# Controller_Schematic.net
KiCad netlist of a schematic drawn in Altium Designer
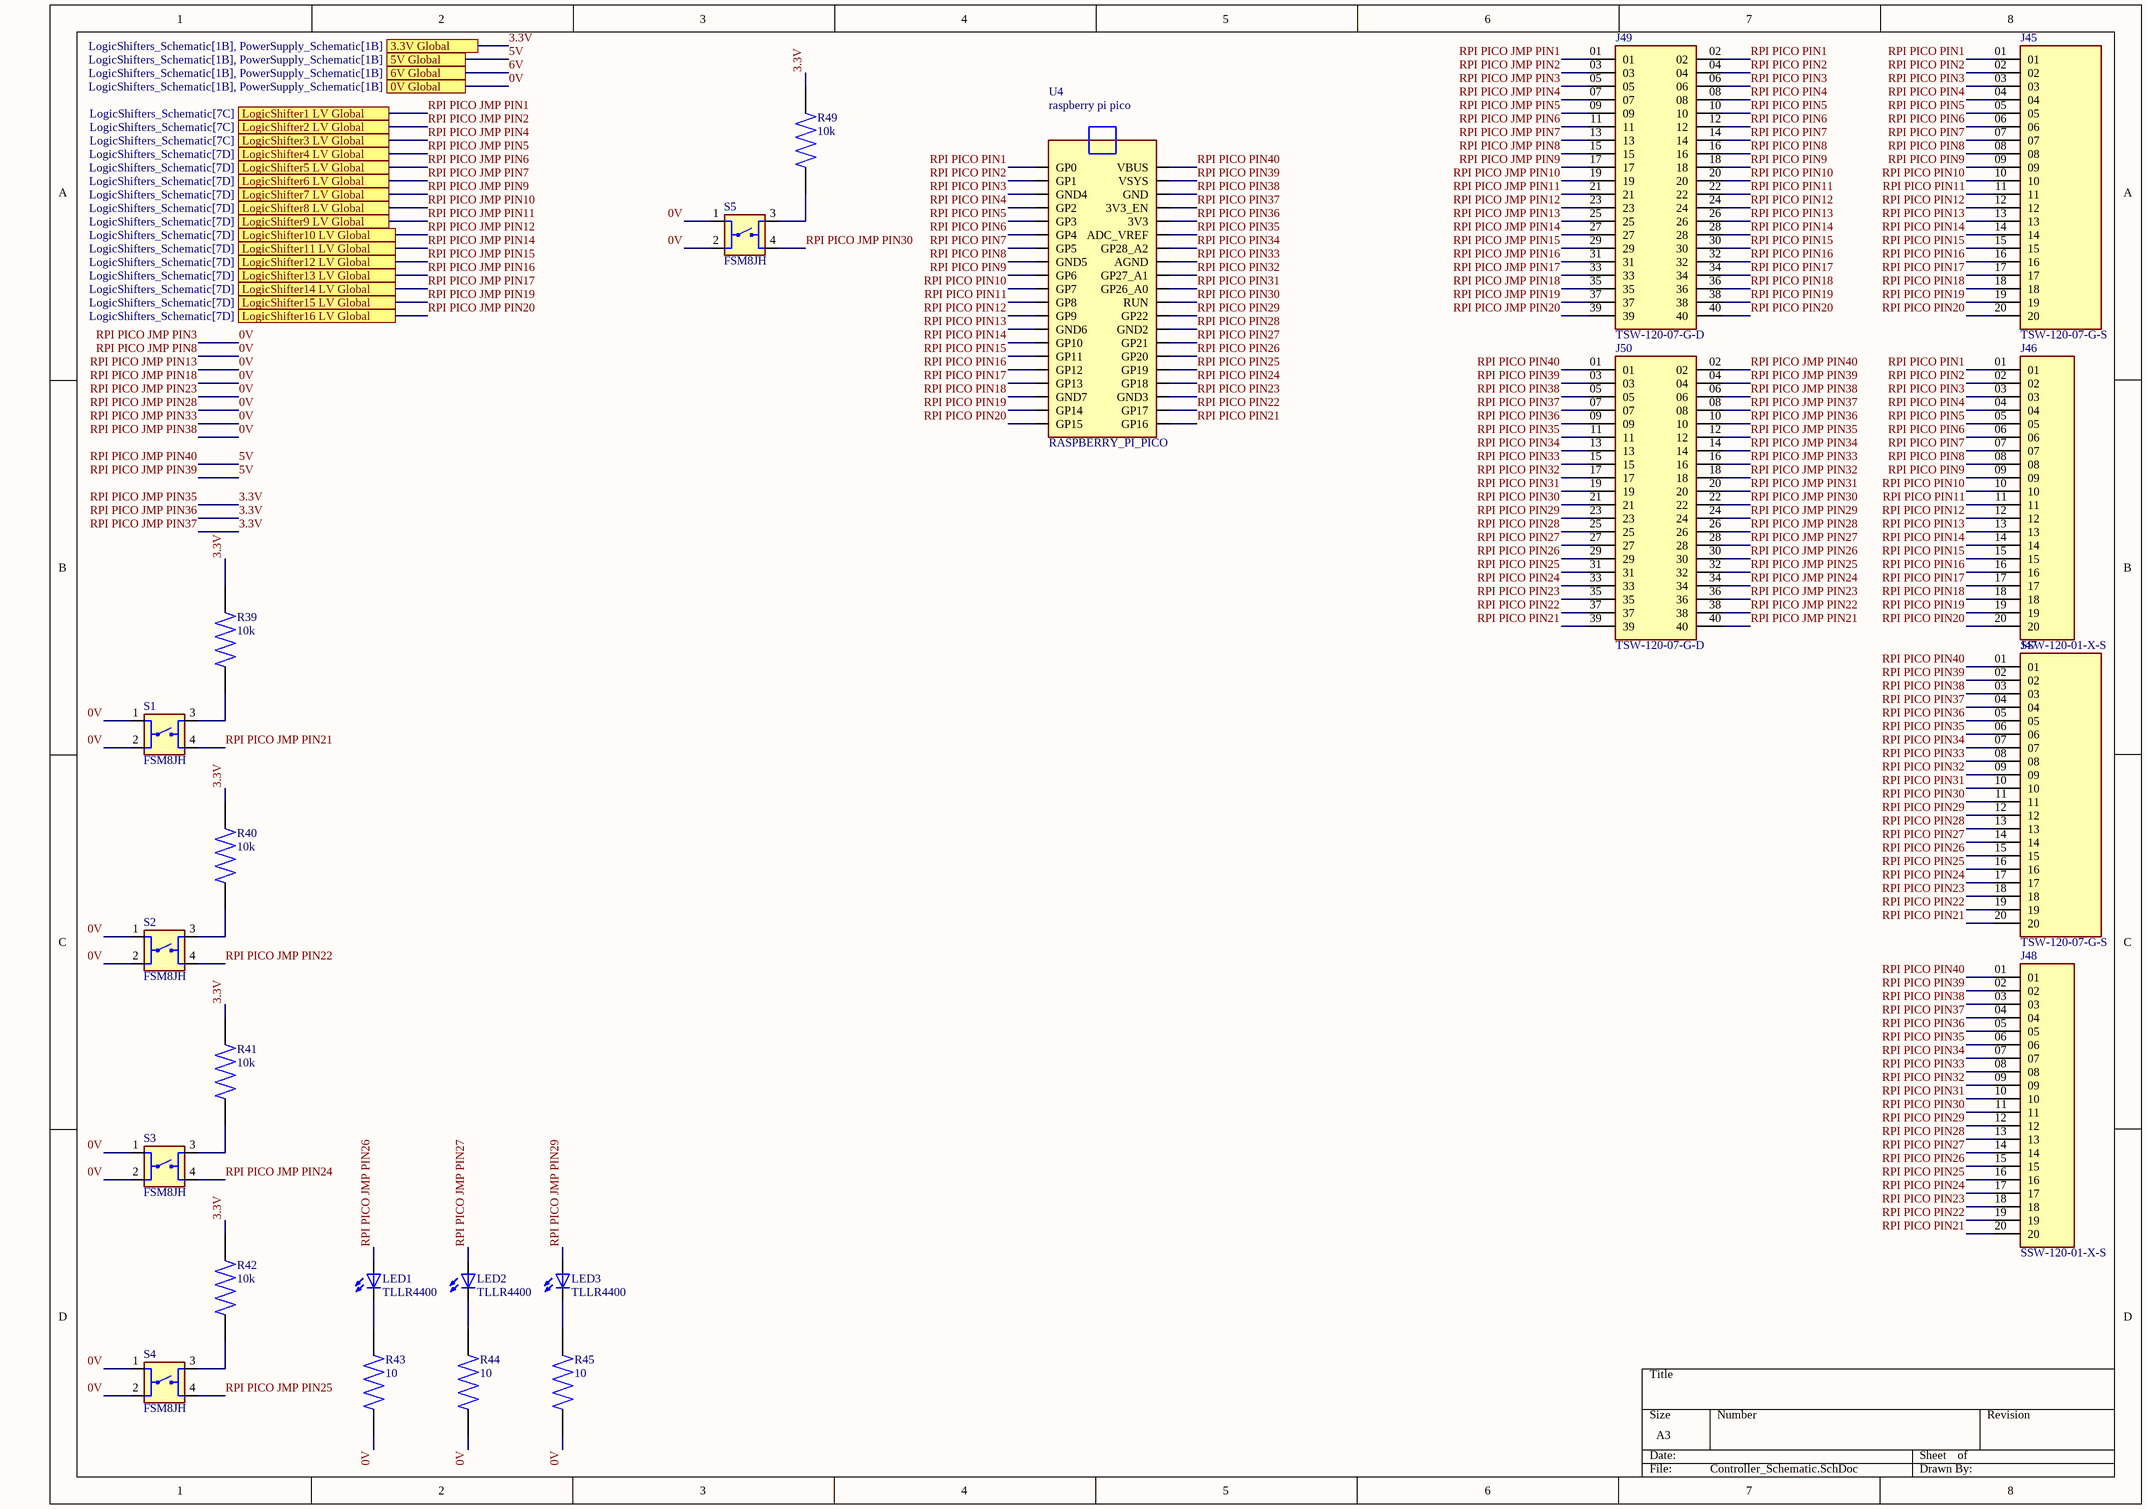
[diagram p0: Controller_Schematic.SchDoc]

(export (version "E")
  (design (tool "Eeschema 10.0.6"))
  (components
    (comp (ref "J45")
      (value "TSW-120-07-G-S")
      (footprint "SAMTEC_TSW-120-07-G-S")
      (fields (field (name "MF") "Samtec"))
      (libsource (lib "TSW-120-07-G-S") (part "TSW-120-07-G-S"))
    )
    (comp (ref "J46")
      (value "SSW-120-01-X-S")
      (footprint "SAMTEC_SSW-120-01-X-S")
      (description "SSW - Samtec 2.54mm Single Row Straight Socket Strip 8.5 Profile - Fast Stock")
      (fields (field (name "MF") "Samtec") (field (name "MP") "SSW-120-01-G-S"))
      (libsource (lib "SSW-120-01-G-S") (part "SSW-120-01-X-S"))
    )
    (comp (ref "J47")
      (value "TSW-120-07-G-S")
      (footprint "SAMTEC_TSW-120-07-G-S")
      (fields (field (name "MF") "Samtec"))
      (libsource (lib "TSW-120-07-G-S") (part "TSW-120-07-G-S"))
    )
    (comp (ref "J48")
      (value "SSW-120-01-X-S")
      (footprint "SAMTEC_SSW-120-01-X-S")
      (description "SSW - Samtec 2.54mm Single Row Straight Socket Strip 8.5 Profile - Fast Stock")
      (fields (field (name "MF") "Samtec") (field (name "MP") "SSW-120-01-G-S"))
      (libsource (lib "SSW-120-01-G-S") (part "SSW-120-01-X-S"))
    )
    (comp (ref "J49")
      (value "TSW-120-07-G-D")
      (footprint "SAMTEC_TSW-120-07-G-D")
      (fields (field (name "MF") "Samtec"))
      (libsource (lib "TSW-120-07-G-D") (part "TSW-120-07-G-D"))
    )
    (comp (ref "J50")
      (value "TSW-120-07-G-D")
      (footprint "SAMTEC_TSW-120-07-G-D")
      (fields (field (name "MF") "Samtec"))
      (libsource (lib "TSW-120-07-G-D") (part "TSW-120-07-G-D"))
    )
    (comp (ref "LED1")
      (value "TLLR4400")
      (footprint "LED3MM")
      (description "Red 619nm LED Indication - Discrete 1.9V Radial")
      (fields (field (name "MF") "Vishay"))
      (libsource (lib "LED-TLLR4400") (part "TLLR4400"))
    )
    (comp (ref "LED2")
      (value "TLLR4400")
      (footprint "LED3MM")
      (description "Red 619nm LED Indication - Discrete 1.9V Radial")
      (fields (field (name "MF") "Vishay"))
      (libsource (lib "LED-TLLR4400") (part "TLLR4400"))
    )
    (comp (ref "LED3")
      (value "TLLR4400")
      (footprint "LED3MM")
      (description "Red 619nm LED Indication - Discrete 1.9V Radial")
      (fields (field (name "MF") "Vishay"))
      (libsource (lib "LED-TLLR4400") (part "TLLR4400"))
    )
    (comp (ref "R39")
      (value "10k")
      (footprint "RESAD700W45L350D185")
      (description "1 MOhms Â±5% 0.25W, 1/4W Through Hole Resistor Axial - Carbon Film")
      (fields (field (name "MF") "TE Connectivity") (field (name "MP") "3-1623927-1"))
      (libsource (lib "RES-DIP-0.25W") (part "3-1623927-1"))
    )
    (comp (ref "R40")
      (value "10k")
      (footprint "RESAD700W45L350D185")
      (description "1 MOhms Â±5% 0.25W, 1/4W Through Hole Resistor Axial - Carbon Film")
      (fields (field (name "MF") "TE Connectivity") (field (name "MP") "3-1623927-1"))
      (libsource (lib "RES-DIP-0.25W") (part "3-1623927-1"))
    )
    (comp (ref "R41")
      (value "10k")
      (footprint "RESAD700W45L350D185")
      (description "1 MOhms Â±5% 0.25W, 1/4W Through Hole Resistor Axial - Carbon Film")
      (fields (field (name "MF") "TE Connectivity") (field (name "MP") "3-1623927-1"))
      (libsource (lib "RES-DIP-0.25W") (part "3-1623927-1"))
    )
    (comp (ref "R42")
      (value "10k")
      (footprint "RESAD700W45L350D185")
      (description "1 MOhms Â±5% 0.25W, 1/4W Through Hole Resistor Axial - Carbon Film")
      (fields (field (name "MF") "TE Connectivity") (field (name "MP") "3-1623927-1"))
      (libsource (lib "RES-DIP-0.25W") (part "3-1623927-1"))
    )
    (comp (ref "R43")
      (value "10")
      (footprint "RESAD700W45L350D185")
      (description "1 MOhms Â±5% 0.25W, 1/4W Through Hole Resistor Axial - Carbon Film")
      (fields (field (name "MF") "TE Connectivity") (field (name "MP") "3-1623927-1"))
      (libsource (lib "RES-DIP-0.25W") (part "3-1623927-1"))
    )
    (comp (ref "R44")
      (value "10")
      (footprint "RESAD700W45L350D185")
      (description "1 MOhms Â±5% 0.25W, 1/4W Through Hole Resistor Axial - Carbon Film")
      (fields (field (name "MF") "TE Connectivity") (field (name "MP") "3-1623927-1"))
      (libsource (lib "RES-DIP-0.25W") (part "3-1623927-1"))
    )
    (comp (ref "R45")
      (value "10")
      (footprint "RESAD700W45L350D185")
      (description "1 MOhms Â±5% 0.25W, 1/4W Through Hole Resistor Axial - Carbon Film")
      (fields (field (name "MF") "TE Connectivity") (field (name "MP") "3-1623927-1"))
      (libsource (lib "RES-DIP-0.25W") (part "3-1623927-1"))
    )
    (comp (ref "R49")
      (value "10k")
      (footprint "RESAD700W45L350D185")
      (description "1 MOhms Â±5% 0.25W, 1/4W Through Hole Resistor Axial - Carbon Film")
      (fields (field (name "MF") "TE Connectivity") (field (name "MP") "3-1623927-1"))
      (libsource (lib "RES-DIP-0.25W") (part "3-1623927-1"))
    )
    (comp (ref "S1")
      (value "FSM8JH")
      (footprint "SW_FSM8JH")
      (description "Tactile Switch SPST-NO Top Actuated Through Hole")
      (fields (field (name "MF") "TE Connectivity"))
      (libsource (lib "PushButton-FSM8JH") (part "FSM8JH"))
    )
    (comp (ref "S2")
      (value "FSM8JH")
      (footprint "SW_FSM8JH")
      (description "Tactile Switch SPST-NO Top Actuated Through Hole")
      (fields (field (name "MF") "TE Connectivity"))
      (libsource (lib "PushButton-FSM8JH") (part "FSM8JH"))
    )
    (comp (ref "S3")
      (value "FSM8JH")
      (footprint "SW_FSM8JH")
      (description "Tactile Switch SPST-NO Top Actuated Through Hole")
      (fields (field (name "MF") "TE Connectivity"))
      (libsource (lib "PushButton-FSM8JH") (part "FSM8JH"))
    )
    (comp (ref "S4")
      (value "FSM8JH")
      (footprint "SW_FSM8JH")
      (description "Tactile Switch SPST-NO Top Actuated Through Hole")
      (fields (field (name "MF") "TE Connectivity"))
      (libsource (lib "PushButton-FSM8JH") (part "FSM8JH"))
    )
    (comp (ref "S5")
      (value "FSM8JH")
      (footprint "SW_FSM8JH")
      (description "Tactile Switch SPST-NO Top Actuated Through Hole")
      (fields (field (name "MF") "TE Connectivity"))
      (libsource (lib "PushButton-FSM8JH") (part "FSM8JH"))
    )
    (comp (ref "U4")
      (value "RASPBERRY_PI_PICO")
      (footprint "RASPBERRY_PI_PICO")
      (fields (field (name "MF") "Raspberry Pi") (field (name "MP") "RASPBERRY PI PICO"))
      (libsource (lib "RASPBERRY_PI_PICO") (part "RASPBERRY_PI_PICO"))
    )
  )
  (nets
    (net (code "1") (name "/0V") (class "Default")
      (node (ref "J49") (pin "05") (pinfunction "05_05") (pintype "passive"))
      (node (ref "J49") (pin "15") (pinfunction "15_15") (pintype "passive"))
      (node (ref "J49") (pin "25") (pinfunction "25_25") (pintype "passive"))
      (node (ref "J49") (pin "35") (pinfunction "35_35") (pintype "passive"))
      (node (ref "J50") (pin "06") (pinfunction "06_06") (pintype "passive"))
      (node (ref "J50") (pin "16") (pinfunction "16_16") (pintype "passive"))
      (node (ref "J50") (pin "26") (pinfunction "26_26") (pintype "passive"))
      (node (ref "J50") (pin "36") (pinfunction "36_36") (pintype "passive"))
      (node (ref "R43") (pin "1") (pinfunction "1_1") (pintype "passive"))
      (node (ref "R44") (pin "1") (pinfunction "1_1") (pintype "passive"))
      (node (ref "R45") (pin "1") (pinfunction "1_1") (pintype "passive"))
      (node (ref "S1") (pin "1") (pinfunction "1_1") (pintype "passive"))
      (node (ref "S1") (pin "2") (pinfunction "2_2") (pintype "passive"))
      (node (ref "S2") (pin "1") (pinfunction "1_1") (pintype "passive"))
      (node (ref "S2") (pin "2") (pinfunction "2_2") (pintype "passive"))
      (node (ref "S3") (pin "1") (pinfunction "1_1") (pintype "passive"))
      (node (ref "S3") (pin "2") (pinfunction "2_2") (pintype "passive"))
      (node (ref "S4") (pin "1") (pinfunction "1_1") (pintype "passive"))
      (node (ref "S4") (pin "2") (pinfunction "2_2") (pintype "passive"))
      (node (ref "S5") (pin "1") (pinfunction "1_1") (pintype "passive"))
      (node (ref "S5") (pin "2") (pinfunction "2_2") (pintype "passive"))
    )
    (net (code "2") (name "/3.3V") (class "Default")
      (node (ref "J50") (pin "08") (pinfunction "08_08") (pintype "passive"))
      (node (ref "J50") (pin "10") (pinfunction "10_10") (pintype "passive"))
      (node (ref "J50") (pin "12") (pinfunction "12_12") (pintype "passive"))
      (node (ref "R39") (pin "2") (pinfunction "2_2") (pintype "passive"))
      (node (ref "R40") (pin "2") (pinfunction "2_2") (pintype "passive"))
      (node (ref "R41") (pin "2") (pinfunction "2_2") (pintype "passive"))
      (node (ref "R42") (pin "2") (pinfunction "2_2") (pintype "passive"))
      (node (ref "R49") (pin "2") (pinfunction "2_2") (pintype "passive"))
    )
    (net (code "3") (name "/5V") (class "Default")
      (node (ref "J50") (pin "02") (pinfunction "02_02") (pintype "passive"))
      (node (ref "J50") (pin "04") (pinfunction "04_04") (pintype "passive"))
    )
    (net (code "5") (name "/RPI PICO JMP PIN1") (class "Default")
      (node (ref "J49") (pin "01") (pinfunction "01_01") (pintype "passive"))
    )
    (net (code "6") (name "/RPI PICO JMP PIN2") (class "Default")
      (node (ref "J49") (pin "03") (pinfunction "03_03") (pintype "passive"))
    )
    (net (code "7") (name "/RPI PICO JMP PIN4") (class "Default")
      (node (ref "J49") (pin "07") (pinfunction "07_07") (pintype "passive"))
    )
    (net (code "8") (name "/RPI PICO JMP PIN5") (class "Default")
      (node (ref "J49") (pin "09") (pinfunction "09_09") (pintype "passive"))
    )
    (net (code "9") (name "/RPI PICO JMP PIN6") (class "Default")
      (node (ref "J49") (pin "11") (pinfunction "11_11") (pintype "passive"))
    )
    (net (code "10") (name "/RPI PICO JMP PIN7") (class "Default")
      (node (ref "J49") (pin "13") (pinfunction "13_13") (pintype "passive"))
    )
    (net (code "11") (name "/RPI PICO JMP PIN9") (class "Default")
      (node (ref "J49") (pin "17") (pinfunction "17_17") (pintype "passive"))
    )
    (net (code "12") (name "/RPI PICO JMP PIN10") (class "Default")
      (node (ref "J49") (pin "19") (pinfunction "19_19") (pintype "passive"))
    )
    (net (code "13") (name "/RPI PICO JMP PIN11") (class "Default")
      (node (ref "J49") (pin "21") (pinfunction "21_21") (pintype "passive"))
    )
    (net (code "14") (name "/RPI PICO JMP PIN12") (class "Default")
      (node (ref "J49") (pin "23") (pinfunction "23_23") (pintype "passive"))
    )
    (net (code "15") (name "/RPI PICO JMP PIN14") (class "Default")
      (node (ref "J49") (pin "27") (pinfunction "27_27") (pintype "passive"))
    )
    (net (code "16") (name "/RPI PICO JMP PIN15") (class "Default")
      (node (ref "J49") (pin "29") (pinfunction "29_29") (pintype "passive"))
    )
    (net (code "17") (name "/RPI PICO JMP PIN16") (class "Default")
      (node (ref "J49") (pin "31") (pinfunction "31_31") (pintype "passive"))
    )
    (net (code "18") (name "/RPI PICO JMP PIN17") (class "Default")
      (node (ref "J49") (pin "33") (pinfunction "33_33") (pintype "passive"))
    )
    (net (code "19") (name "/RPI PICO JMP PIN19") (class "Default")
      (node (ref "J49") (pin "37") (pinfunction "37_37") (pintype "passive"))
    )
    (net (code "20") (name "/RPI PICO JMP PIN20") (class "Default")
      (node (ref "J49") (pin "39") (pinfunction "39_39") (pintype "passive"))
    )
    (net (code "21") (name "/RPI PICO JMP PIN21") (class "Default")
      (node (ref "J50") (pin "40") (pinfunction "40_40") (pintype "passive"))
      (node (ref "S1") (pin "4") (pinfunction "4_4") (pintype "passive"))
    )
    (net (code "22") (name "/RPI PICO JMP PIN22") (class "Default")
      (node (ref "J50") (pin "38") (pinfunction "38_38") (pintype "passive"))
      (node (ref "S2") (pin "4") (pinfunction "4_4") (pintype "passive"))
    )
    (net (code "23") (name "/RPI PICO JMP PIN24") (class "Default")
      (node (ref "J50") (pin "34") (pinfunction "34_34") (pintype "passive"))
      (node (ref "S3") (pin "4") (pinfunction "4_4") (pintype "passive"))
    )
    (net (code "24") (name "/RPI PICO JMP PIN25") (class "Default")
      (node (ref "J50") (pin "32") (pinfunction "32_32") (pintype "passive"))
      (node (ref "S4") (pin "4") (pinfunction "4_4") (pintype "passive"))
    )
    (net (code "25") (name "/RPI PICO JMP PIN26") (class "Default")
      (node (ref "J50") (pin "30") (pinfunction "30_30") (pintype "passive"))
      (node (ref "LED1") (pin "A") (pinfunction "A_A") (pintype "passive"))
    )
    (net (code "26") (name "/RPI PICO JMP PIN27") (class "Default")
      (node (ref "J50") (pin "28") (pinfunction "28_28") (pintype "passive"))
      (node (ref "LED2") (pin "A") (pinfunction "A_A") (pintype "passive"))
    )
    (net (code "27") (name "/RPI PICO JMP PIN29") (class "Default")
      (node (ref "J50") (pin "24") (pinfunction "24_24") (pintype "passive"))
      (node (ref "LED3") (pin "A") (pinfunction "A_A") (pintype "passive"))
    )
    (net (code "28") (name "/RPI PICO JMP PIN30") (class "Default")
      (node (ref "J50") (pin "22") (pinfunction "22_22") (pintype "passive"))
      (node (ref "S5") (pin "4") (pinfunction "4_4") (pintype "passive"))
    )
    (net (code "29") (name "/RPI PICO JMP PIN31") (class "Default")
      (node (ref "J50") (pin "20") (pinfunction "20_20") (pintype "passive"))
    )
    (net (code "30") (name "/RPI PICO JMP PIN32") (class "Default")
      (node (ref "J50") (pin "18") (pinfunction "18_18") (pintype "passive"))
    )
    (net (code "31") (name "/RPI PICO JMP PIN34") (class "Default")
      (node (ref "J50") (pin "14") (pinfunction "14_14") (pintype "passive"))
    )
    (net (code "32") (name "/RPI PICO PIN1") (class "Default")
      (node (ref "J45") (pin "01") (pinfunction "01_01") (pintype "passive"))
      (node (ref "J46") (pin "01") (pinfunction "01_01") (pintype "passive"))
      (node (ref "J49") (pin "02") (pinfunction "02_02") (pintype "passive"))
      (node (ref "U4") (pin "GP0") (pinfunction "GP0_GP0") (pintype "bidirectional"))
    )
    (net (code "33") (name "/RPI PICO PIN2") (class "Default")
      (node (ref "J45") (pin "02") (pinfunction "02_02") (pintype "passive"))
      (node (ref "J46") (pin "02") (pinfunction "02_02") (pintype "passive"))
      (node (ref "J49") (pin "04") (pinfunction "04_04") (pintype "passive"))
      (node (ref "U4") (pin "GP1") (pinfunction "GP1_GP1") (pintype "bidirectional"))
    )
    (net (code "34") (name "/RPI PICO PIN3") (class "Default")
      (node (ref "J45") (pin "03") (pinfunction "03_03") (pintype "passive"))
      (node (ref "J46") (pin "03") (pinfunction "03_03") (pintype "passive"))
      (node (ref "J49") (pin "06") (pinfunction "06_06") (pintype "passive"))
      (node (ref "U4") (pin "GND4") (pinfunction "GND4_GND4") (pintype "bidirectional"))
    )
    (net (code "35") (name "/RPI PICO PIN4") (class "Default")
      (node (ref "J45") (pin "04") (pinfunction "04_04") (pintype "passive"))
      (node (ref "J46") (pin "04") (pinfunction "04_04") (pintype "passive"))
      (node (ref "J49") (pin "08") (pinfunction "08_08") (pintype "passive"))
      (node (ref "U4") (pin "GP2") (pinfunction "GP2_GP2") (pintype "bidirectional"))
    )
    (net (code "36") (name "/RPI PICO PIN5") (class "Default")
      (node (ref "J45") (pin "05") (pinfunction "05_05") (pintype "passive"))
      (node (ref "J46") (pin "05") (pinfunction "05_05") (pintype "passive"))
      (node (ref "J49") (pin "10") (pinfunction "10_10") (pintype "passive"))
      (node (ref "U4") (pin "GP3") (pinfunction "GP3_GP3") (pintype "bidirectional"))
    )
    (net (code "37") (name "/RPI PICO PIN6") (class "Default")
      (node (ref "J45") (pin "06") (pinfunction "06_06") (pintype "passive"))
      (node (ref "J46") (pin "06") (pinfunction "06_06") (pintype "passive"))
      (node (ref "J49") (pin "12") (pinfunction "12_12") (pintype "passive"))
      (node (ref "U4") (pin "GP4") (pinfunction "GP4_GP4") (pintype "bidirectional"))
    )
    (net (code "38") (name "/RPI PICO PIN7") (class "Default")
      (node (ref "J45") (pin "07") (pinfunction "07_07") (pintype "passive"))
      (node (ref "J46") (pin "07") (pinfunction "07_07") (pintype "passive"))
      (node (ref "J49") (pin "14") (pinfunction "14_14") (pintype "passive"))
      (node (ref "U4") (pin "GP5") (pinfunction "GP5_GP5") (pintype "bidirectional"))
    )
    (net (code "39") (name "/RPI PICO PIN8") (class "Default")
      (node (ref "J45") (pin "08") (pinfunction "08_08") (pintype "passive"))
      (node (ref "J46") (pin "08") (pinfunction "08_08") (pintype "passive"))
      (node (ref "J49") (pin "16") (pinfunction "16_16") (pintype "passive"))
      (node (ref "U4") (pin "GND5") (pinfunction "GND5_GND5") (pintype "bidirectional"))
    )
    (net (code "40") (name "/RPI PICO PIN9") (class "Default")
      (node (ref "J45") (pin "09") (pinfunction "09_09") (pintype "passive"))
      (node (ref "J46") (pin "09") (pinfunction "09_09") (pintype "passive"))
      (node (ref "J49") (pin "18") (pinfunction "18_18") (pintype "passive"))
      (node (ref "U4") (pin "GP6") (pinfunction "GP6_GP6") (pintype "bidirectional"))
    )
    (net (code "41") (name "/RPI PICO PIN10") (class "Default")
      (node (ref "J45") (pin "10") (pinfunction "10_10") (pintype "passive"))
      (node (ref "J46") (pin "10") (pinfunction "10_10") (pintype "passive"))
      (node (ref "J49") (pin "20") (pinfunction "20_20") (pintype "passive"))
      (node (ref "U4") (pin "GP7") (pinfunction "GP7_GP7") (pintype "bidirectional"))
    )
    (net (code "42") (name "/RPI PICO PIN11") (class "Default")
      (node (ref "J45") (pin "11") (pinfunction "11_11") (pintype "passive"))
      (node (ref "J46") (pin "11") (pinfunction "11_11") (pintype "passive"))
      (node (ref "J49") (pin "22") (pinfunction "22_22") (pintype "passive"))
      (node (ref "U4") (pin "GP8") (pinfunction "GP8_GP8") (pintype "bidirectional"))
    )
    (net (code "43") (name "/RPI PICO PIN12") (class "Default")
      (node (ref "J45") (pin "12") (pinfunction "12_12") (pintype "passive"))
      (node (ref "J46") (pin "12") (pinfunction "12_12") (pintype "passive"))
      (node (ref "J49") (pin "24") (pinfunction "24_24") (pintype "passive"))
      (node (ref "U4") (pin "GP9") (pinfunction "GP9_GP9") (pintype "bidirectional"))
    )
    (net (code "44") (name "/RPI PICO PIN13") (class "Default")
      (node (ref "J45") (pin "13") (pinfunction "13_13") (pintype "passive"))
      (node (ref "J46") (pin "13") (pinfunction "13_13") (pintype "passive"))
      (node (ref "J49") (pin "26") (pinfunction "26_26") (pintype "passive"))
      (node (ref "U4") (pin "GND6") (pinfunction "GND6_GND6") (pintype "bidirectional"))
    )
    (net (code "45") (name "/RPI PICO PIN14") (class "Default")
      (node (ref "J45") (pin "14") (pinfunction "14_14") (pintype "passive"))
      (node (ref "J46") (pin "14") (pinfunction "14_14") (pintype "passive"))
      (node (ref "J49") (pin "28") (pinfunction "28_28") (pintype "passive"))
      (node (ref "U4") (pin "GP10") (pinfunction "GP10_GP10") (pintype "bidirectional"))
    )
    (net (code "46") (name "/RPI PICO PIN15") (class "Default")
      (node (ref "J45") (pin "15") (pinfunction "15_15") (pintype "passive"))
      (node (ref "J46") (pin "15") (pinfunction "15_15") (pintype "passive"))
      (node (ref "J49") (pin "30") (pinfunction "30_30") (pintype "passive"))
      (node (ref "U4") (pin "GP11") (pinfunction "GP11_GP11") (pintype "bidirectional"))
    )
    (net (code "47") (name "/RPI PICO PIN16") (class "Default")
      (node (ref "J45") (pin "16") (pinfunction "16_16") (pintype "passive"))
      (node (ref "J46") (pin "16") (pinfunction "16_16") (pintype "passive"))
      (node (ref "J49") (pin "32") (pinfunction "32_32") (pintype "passive"))
      (node (ref "U4") (pin "GP12") (pinfunction "GP12_GP12") (pintype "bidirectional"))
    )
    (net (code "48") (name "/RPI PICO PIN17") (class "Default")
      (node (ref "J45") (pin "17") (pinfunction "17_17") (pintype "passive"))
      (node (ref "J46") (pin "17") (pinfunction "17_17") (pintype "passive"))
      (node (ref "J49") (pin "34") (pinfunction "34_34") (pintype "passive"))
      (node (ref "U4") (pin "GP13") (pinfunction "GP13_GP13") (pintype "bidirectional"))
    )
    (net (code "49") (name "/RPI PICO PIN18") (class "Default")
      (node (ref "J45") (pin "18") (pinfunction "18_18") (pintype "passive"))
      (node (ref "J46") (pin "18") (pinfunction "18_18") (pintype "passive"))
      (node (ref "J49") (pin "36") (pinfunction "36_36") (pintype "passive"))
      (node (ref "U4") (pin "GND7") (pinfunction "GND7_GND7") (pintype "bidirectional"))
    )
    (net (code "50") (name "/RPI PICO PIN19") (class "Default")
      (node (ref "J45") (pin "19") (pinfunction "19_19") (pintype "passive"))
      (node (ref "J46") (pin "19") (pinfunction "19_19") (pintype "passive"))
      (node (ref "J49") (pin "38") (pinfunction "38_38") (pintype "passive"))
      (node (ref "U4") (pin "GP14") (pinfunction "GP14_GP14") (pintype "bidirectional"))
    )
    (net (code "51") (name "/RPI PICO PIN20") (class "Default")
      (node (ref "J45") (pin "20") (pinfunction "20_20") (pintype "passive"))
      (node (ref "J46") (pin "20") (pinfunction "20_20") (pintype "passive"))
      (node (ref "J49") (pin "40") (pinfunction "40_40") (pintype "passive"))
      (node (ref "U4") (pin "GP15") (pinfunction "GP15_GP15") (pintype "bidirectional"))
    )
    (net (code "52") (name "/RPI PICO PIN21") (class "Default")
      (node (ref "J47") (pin "20") (pinfunction "20_20") (pintype "passive"))
      (node (ref "J48") (pin "20") (pinfunction "20_20") (pintype "passive"))
      (node (ref "J50") (pin "39") (pinfunction "39_39") (pintype "passive"))
      (node (ref "U4") (pin "GP16") (pinfunction "GP16_GP16") (pintype "bidirectional"))
    )
    (net (code "53") (name "/RPI PICO PIN22") (class "Default")
      (node (ref "J47") (pin "19") (pinfunction "19_19") (pintype "passive"))
      (node (ref "J48") (pin "19") (pinfunction "19_19") (pintype "passive"))
      (node (ref "J50") (pin "37") (pinfunction "37_37") (pintype "passive"))
      (node (ref "U4") (pin "GP17") (pinfunction "GP17_GP17") (pintype "bidirectional"))
    )
    (net (code "54") (name "/RPI PICO PIN23") (class "Default")
      (node (ref "J47") (pin "18") (pinfunction "18_18") (pintype "passive"))
      (node (ref "J48") (pin "18") (pinfunction "18_18") (pintype "passive"))
      (node (ref "J50") (pin "35") (pinfunction "35_35") (pintype "passive"))
      (node (ref "U4") (pin "GND3") (pinfunction "GND3_GND3") (pintype "bidirectional"))
    )
    (net (code "55") (name "/RPI PICO PIN24") (class "Default")
      (node (ref "J47") (pin "17") (pinfunction "17_17") (pintype "passive"))
      (node (ref "J48") (pin "17") (pinfunction "17_17") (pintype "passive"))
      (node (ref "J50") (pin "33") (pinfunction "33_33") (pintype "passive"))
      (node (ref "U4") (pin "GP18") (pinfunction "GP18_GP18") (pintype "bidirectional"))
    )
    (net (code "56") (name "/RPI PICO PIN25") (class "Default")
      (node (ref "J47") (pin "16") (pinfunction "16_16") (pintype "passive"))
      (node (ref "J48") (pin "16") (pinfunction "16_16") (pintype "passive"))
      (node (ref "J50") (pin "31") (pinfunction "31_31") (pintype "passive"))
      (node (ref "U4") (pin "GP19") (pinfunction "GP19_GP19") (pintype "bidirectional"))
    )
    (net (code "57") (name "/RPI PICO PIN26") (class "Default")
      (node (ref "J47") (pin "15") (pinfunction "15_15") (pintype "passive"))
      (node (ref "J48") (pin "15") (pinfunction "15_15") (pintype "passive"))
      (node (ref "J50") (pin "29") (pinfunction "29_29") (pintype "passive"))
      (node (ref "U4") (pin "GP20") (pinfunction "GP20_GP20") (pintype "bidirectional"))
    )
    (net (code "58") (name "/RPI PICO PIN27") (class "Default")
      (node (ref "J47") (pin "14") (pinfunction "14_14") (pintype "passive"))
      (node (ref "J48") (pin "14") (pinfunction "14_14") (pintype "passive"))
      (node (ref "J50") (pin "27") (pinfunction "27_27") (pintype "passive"))
      (node (ref "U4") (pin "GP21") (pinfunction "GP21_GP21") (pintype "bidirectional"))
    )
    (net (code "59") (name "/RPI PICO PIN28") (class "Default")
      (node (ref "J47") (pin "13") (pinfunction "13_13") (pintype "passive"))
      (node (ref "J48") (pin "13") (pinfunction "13_13") (pintype "passive"))
      (node (ref "J50") (pin "25") (pinfunction "25_25") (pintype "passive"))
      (node (ref "U4") (pin "GND2") (pinfunction "GND2_GND2") (pintype "bidirectional"))
    )
    (net (code "60") (name "/RPI PICO PIN29") (class "Default")
      (node (ref "J47") (pin "12") (pinfunction "12_12") (pintype "passive"))
      (node (ref "J48") (pin "12") (pinfunction "12_12") (pintype "passive"))
      (node (ref "J50") (pin "23") (pinfunction "23_23") (pintype "passive"))
      (node (ref "U4") (pin "GP22") (pinfunction "GP22_GP22") (pintype "bidirectional"))
    )
    (net (code "61") (name "/RPI PICO PIN30") (class "Default")
      (node (ref "J47") (pin "11") (pinfunction "11_11") (pintype "passive"))
      (node (ref "J48") (pin "11") (pinfunction "11_11") (pintype "passive"))
      (node (ref "J50") (pin "21") (pinfunction "21_21") (pintype "passive"))
      (node (ref "U4") (pin "RUN") (pinfunction "RUN_RUN") (pintype "bidirectional"))
    )
    (net (code "62") (name "/RPI PICO PIN31") (class "Default")
      (node (ref "J47") (pin "10") (pinfunction "10_10") (pintype "passive"))
      (node (ref "J48") (pin "10") (pinfunction "10_10") (pintype "passive"))
      (node (ref "J50") (pin "19") (pinfunction "19_19") (pintype "passive"))
      (node (ref "U4") (pin "GP26_A0") (pinfunction "GP26_A0_GP26_A0") (pintype "bidirectional"))
    )
    (net (code "63") (name "/RPI PICO PIN32") (class "Default")
      (node (ref "J47") (pin "09") (pinfunction "09_09") (pintype "passive"))
      (node (ref "J48") (pin "09") (pinfunction "09_09") (pintype "passive"))
      (node (ref "J50") (pin "17") (pinfunction "17_17") (pintype "passive"))
      (node (ref "U4") (pin "GP27_A1") (pinfunction "GP27_A1_GP27_A1") (pintype "bidirectional"))
    )
    (net (code "64") (name "/RPI PICO PIN33") (class "Default")
      (node (ref "J47") (pin "08") (pinfunction "08_08") (pintype "passive"))
      (node (ref "J48") (pin "08") (pinfunction "08_08") (pintype "passive"))
      (node (ref "J50") (pin "15") (pinfunction "15_15") (pintype "passive"))
      (node (ref "U4") (pin "AGND") (pinfunction "AGND_AGND") (pintype "bidirectional"))
    )
    (net (code "65") (name "/RPI PICO PIN34") (class "Default")
      (node (ref "J47") (pin "07") (pinfunction "07_07") (pintype "passive"))
      (node (ref "J48") (pin "07") (pinfunction "07_07") (pintype "passive"))
      (node (ref "J50") (pin "13") (pinfunction "13_13") (pintype "passive"))
      (node (ref "U4") (pin "GP28_A2") (pinfunction "GP28_A2_GP28_A2") (pintype "bidirectional"))
    )
    (net (code "66") (name "/RPI PICO PIN35") (class "Default")
      (node (ref "J47") (pin "06") (pinfunction "06_06") (pintype "passive"))
      (node (ref "J48") (pin "06") (pinfunction "06_06") (pintype "passive"))
      (node (ref "J50") (pin "11") (pinfunction "11_11") (pintype "passive"))
      (node (ref "U4") (pin "ADC_VREF") (pinfunction "ADC_VREF_ADC_VREF") (pintype "bidirectional"))
    )
    (net (code "67") (name "/RPI PICO PIN36") (class "Default")
      (node (ref "J47") (pin "05") (pinfunction "05_05") (pintype "passive"))
      (node (ref "J48") (pin "05") (pinfunction "05_05") (pintype "passive"))
      (node (ref "J50") (pin "09") (pinfunction "09_09") (pintype "passive"))
      (node (ref "U4") (pin "3V3") (pinfunction "3V3_3V3") (pintype "bidirectional"))
    )
    (net (code "68") (name "/RPI PICO PIN37") (class "Default")
      (node (ref "J47") (pin "04") (pinfunction "04_04") (pintype "passive"))
      (node (ref "J48") (pin "04") (pinfunction "04_04") (pintype "passive"))
      (node (ref "J50") (pin "07") (pinfunction "07_07") (pintype "passive"))
      (node (ref "U4") (pin "3V3_EN") (pinfunction "3V3_EN_3V3_EN") (pintype "bidirectional"))
    )
    (net (code "69") (name "/RPI PICO PIN38") (class "Default")
      (node (ref "J47") (pin "03") (pinfunction "03_03") (pintype "passive"))
      (node (ref "J48") (pin "03") (pinfunction "03_03") (pintype "passive"))
      (node (ref "J50") (pin "05") (pinfunction "05_05") (pintype "passive"))
      (node (ref "U4") (pin "GND") (pinfunction "GND_GND") (pintype "bidirectional"))
    )
    (net (code "70") (name "/RPI PICO PIN39") (class "Default")
      (node (ref "J47") (pin "02") (pinfunction "02_02") (pintype "passive"))
      (node (ref "J48") (pin "02") (pinfunction "02_02") (pintype "passive"))
      (node (ref "J50") (pin "03") (pinfunction "03_03") (pintype "passive"))
      (node (ref "U4") (pin "VSYS") (pinfunction "VSYS_VSYS") (pintype "bidirectional"))
    )
    (net (code "71") (name "/RPI PICO PIN40") (class "Default")
      (node (ref "J47") (pin "01") (pinfunction "01_01") (pintype "passive"))
      (node (ref "J48") (pin "01") (pinfunction "01_01") (pintype "passive"))
      (node (ref "J50") (pin "01") (pinfunction "01_01") (pintype "passive"))
      (node (ref "U4") (pin "VBUS") (pinfunction "VBUS_VBUS") (pintype "bidirectional"))
    )
    (net (code "72") (name "Net-(LED1-C)") (class "Default")
      (node (ref "LED1") (pin "K") (pinfunction "C_K") (pintype "passive"))
      (node (ref "R43") (pin "2") (pinfunction "2_2") (pintype "passive"))
    )
    (net (code "73") (name "Net-(LED2-C)") (class "Default")
      (node (ref "LED2") (pin "K") (pinfunction "C_K") (pintype "passive"))
      (node (ref "R44") (pin "2") (pinfunction "2_2") (pintype "passive"))
    )
    (net (code "74") (name "Net-(LED3-C)") (class "Default")
      (node (ref "LED3") (pin "K") (pinfunction "C_K") (pintype "passive"))
      (node (ref "R45") (pin "2") (pinfunction "2_2") (pintype "passive"))
    )
    (net (code "75") (name "Net-(R39-Pad1)") (class "Default")
      (node (ref "R39") (pin "1") (pinfunction "1_1") (pintype "passive"))
      (node (ref "S1") (pin "3") (pinfunction "3_3") (pintype "passive"))
    )
    (net (code "76") (name "Net-(R40-Pad1)") (class "Default")
      (node (ref "R40") (pin "1") (pinfunction "1_1") (pintype "passive"))
      (node (ref "S2") (pin "3") (pinfunction "3_3") (pintype "passive"))
    )
    (net (code "77") (name "Net-(R41-Pad1)") (class "Default")
      (node (ref "R41") (pin "1") (pinfunction "1_1") (pintype "passive"))
      (node (ref "S3") (pin "3") (pinfunction "3_3") (pintype "passive"))
    )
    (net (code "78") (name "Net-(R42-Pad1)") (class "Default")
      (node (ref "R42") (pin "1") (pinfunction "1_1") (pintype "passive"))
      (node (ref "S4") (pin "3") (pinfunction "3_3") (pintype "passive"))
    )
    (net (code "79") (name "Net-(R49-Pad1)") (class "Default")
      (node (ref "R49") (pin "1") (pinfunction "1_1") (pintype "passive"))
      (node (ref "S5") (pin "3") (pinfunction "3_3") (pintype "passive"))
    )
  )
)
